# Sheet1.net
KiCad netlist of a schematic drawn in Altium Designer
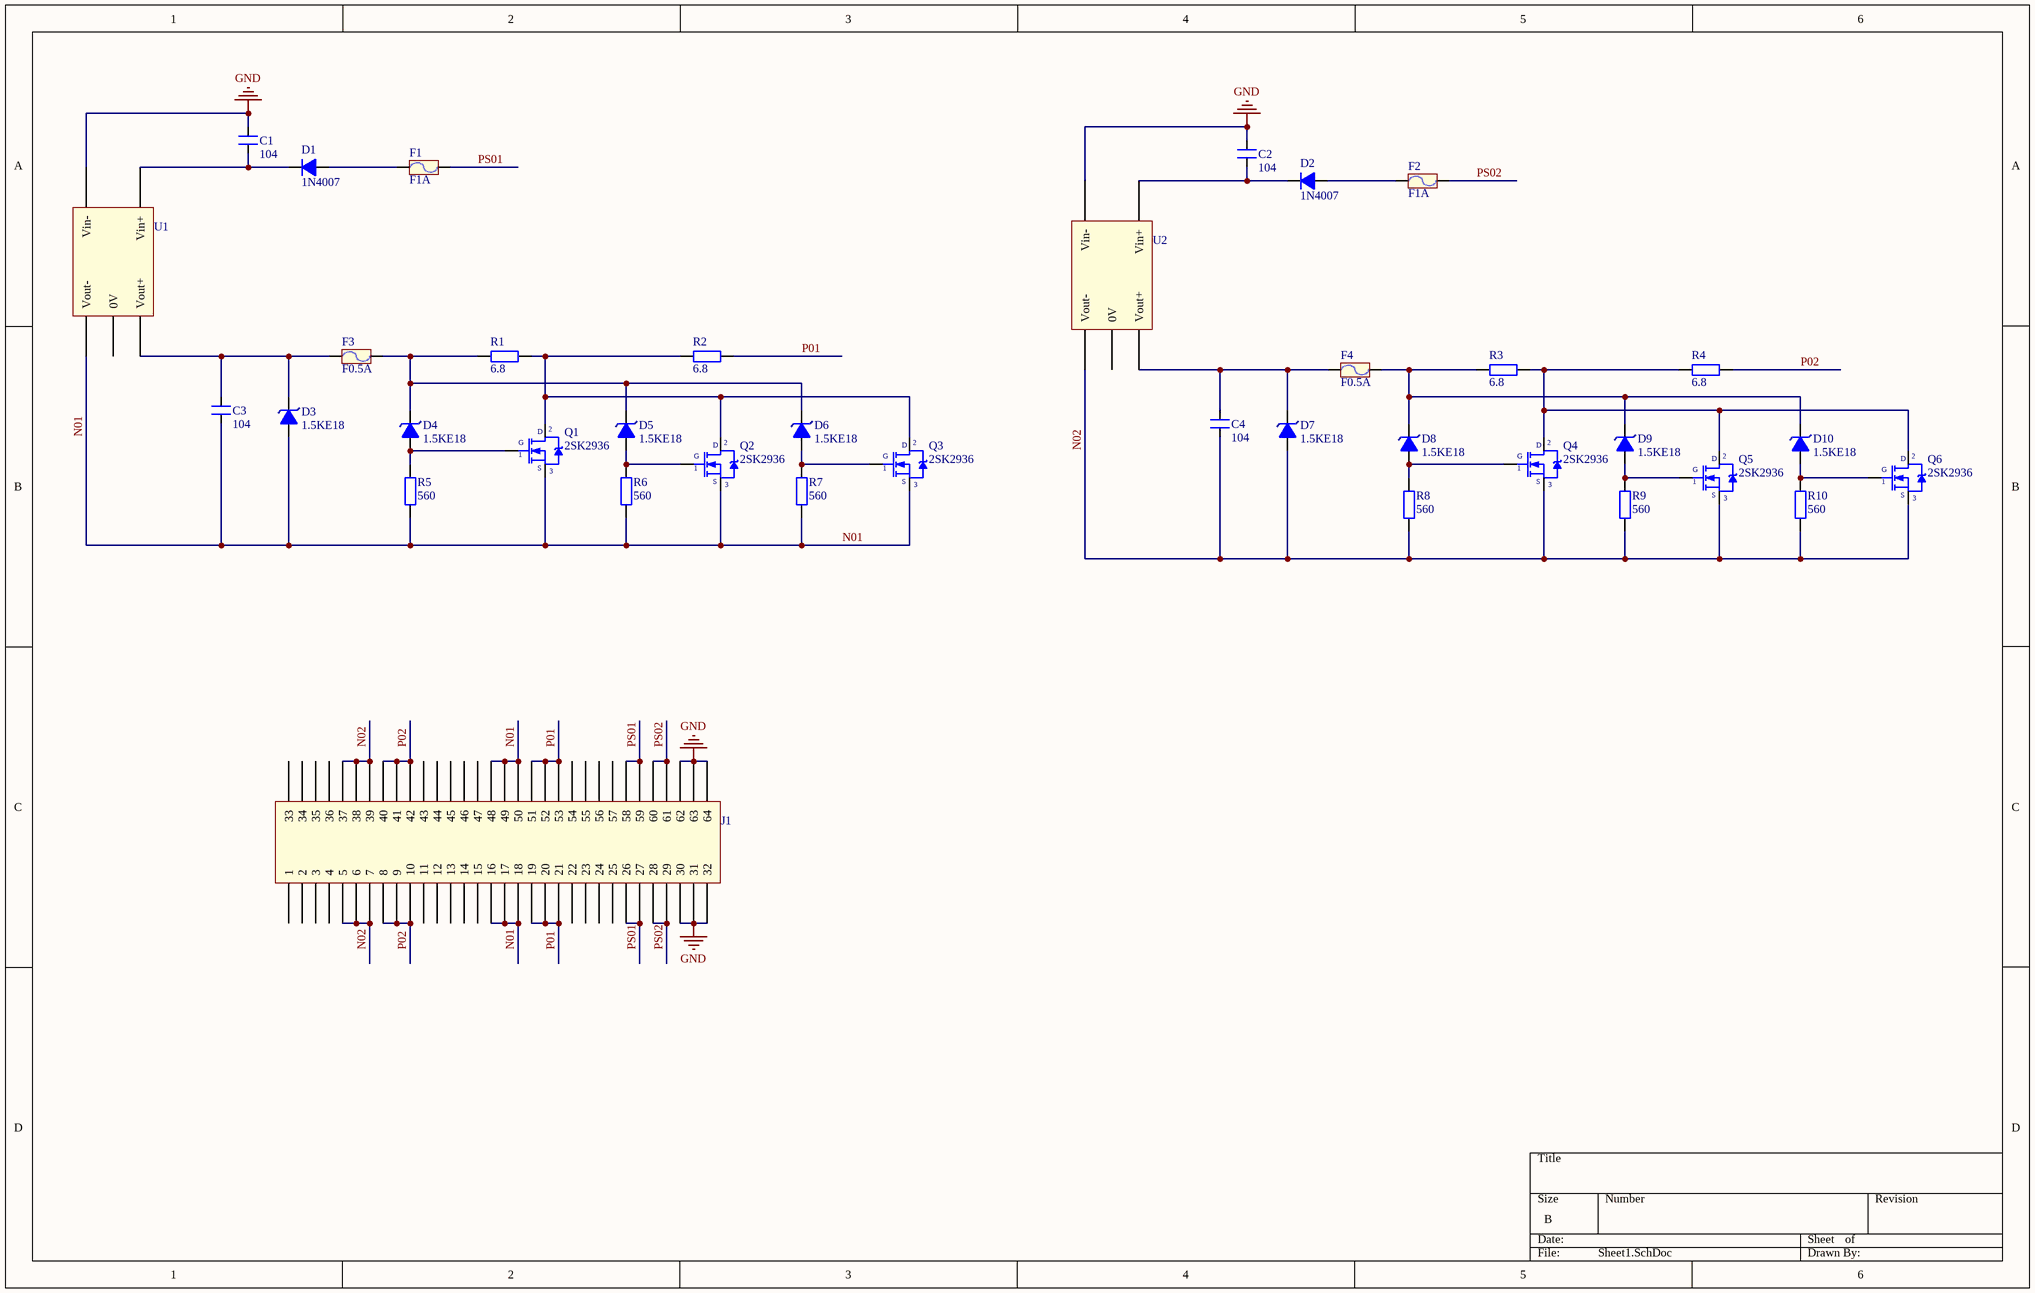
[diagram p0: Sheet1.SchDoc]

(export (version "E")
  (design (tool "Eeschema 10.0.6"))
  (components
    (comp (ref "C1")
      (value "104")
      (footprint "CN1")
      (description "Cremic For Xtal 1pF => 100pF")
      (libsource (lib "Binh_BK") (part "CAP"))
    )
    (comp (ref "C2")
      (value "104")
      (footprint "CN1")
      (description "Cremic For Xtal 1pF => 100pF")
      (libsource (lib "Binh_BK") (part "CAP"))
    )
    (comp (ref "C3")
      (value "104")
      (footprint "CN1")
      (description "Cremic For Xtal 1pF => 100pF")
      (libsource (lib "Binh_BK") (part "CAP"))
    )
    (comp (ref "C4")
      (value "104")
      (footprint "CN1")
      (description "Cremic For Xtal 1pF => 100pF")
      (libsource (lib "Binh_BK") (part "CAP"))
    )
    (comp (ref "D1")
      (value "1N4007")
      (footprint "D1A")
      (description "Diode 1A")
      (libsource (lib "Binh_BK") (part "D1A"))
    )
    (comp (ref "D2")
      (value "1N4007")
      (footprint "D1A")
      (description "Diode 1A")
      (libsource (lib "Binh_BK") (part "D1A"))
    )
    (comp (ref "D3") (value "1.5KE18") (footprint "D1A") (libsource (lib "Binh_BK") (part "Zener")))
    (comp (ref "D4") (value "1.5KE18") (footprint "D1A") (libsource (lib "Binh_BK") (part "Zener")))
    (comp (ref "D5") (value "1.5KE18") (footprint "D1A") (libsource (lib "Binh_BK") (part "Zener")))
    (comp (ref "D6") (value "1.5KE18") (footprint "D1A") (libsource (lib "Binh_BK") (part "Zener")))
    (comp (ref "D7") (value "1.5KE18") (footprint "D1A") (libsource (lib "Binh_BK") (part "Zener")))
    (comp (ref "D8") (value "1.5KE18") (footprint "D1A") (libsource (lib "Binh_BK") (part "Zener")))
    (comp (ref "D9") (value "1.5KE18") (footprint "D1A") (libsource (lib "Binh_BK") (part "Zener")))
    (comp (ref "D10") (value "1.5KE18") (footprint "D1A") (libsource (lib "Binh_BK") (part "Zener")))
    (comp (ref "F1")
      (value "F1A")
      (footprint "Fuse")
      (description "Fuse")
      (fields (field (name "DESIGNED BY") "VanDungEvn"))
      (libsource (lib "") (part "Fuse_1"))
    )
    (comp (ref "F2")
      (value "F1A")
      (footprint "Fuse")
      (description "Fuse")
      (fields (field (name "DESIGNED BY") "VanDungEvn"))
      (libsource (lib "") (part "Fuse_1"))
    )
    (comp (ref "F3")
      (value "F0.5A")
      (footprint "Fuse")
      (description "Fuse")
      (fields (field (name "DESIGNED BY") "VanDungEvn"))
      (libsource (lib "Binh_BK") (part "Fuse"))
    )
    (comp (ref "F4")
      (value "F0.5A")
      (footprint "Fuse")
      (description "Fuse")
      (fields (field (name "DESIGNED BY") "VanDungEvn"))
      (libsource (lib "Binh_BK") (part "Fuse"))
    )
    (comp (ref "J1")
      (value "Header 32x2")
      (footprint "Header32x2")
      (libsource (lib "dung_maker_2018") (part "Header 32x2"))
    )
    (comp (ref "Q1")
      (value "2SK2936")
      (footprint "QTO-220")
      (description "MOSFET N - CHANNEL 500V - 0.75 - 8A - TO-220")
      (libsource (lib "Binh_BK") (part "IRF840"))
    )
    (comp (ref "Q2")
      (value "2SK2936")
      (footprint "QTO-220")
      (description "MOSFET N - CHANNEL 500V - 0.75 - 8A - TO-220")
      (libsource (lib "Binh_BK") (part "IRF840"))
    )
    (comp (ref "Q3")
      (value "2SK2936")
      (footprint "QTO-220")
      (description "MOSFET N - CHANNEL 500V - 0.75 - 8A - TO-220")
      (libsource (lib "Binh_BK") (part "IRF840"))
    )
    (comp (ref "Q4")
      (value "2SK2936")
      (footprint "QTO-220")
      (description "MOSFET N - CHANNEL 500V - 0.75 - 8A - TO-220")
      (libsource (lib "Binh_BK") (part "IRF840"))
    )
    (comp (ref "Q5")
      (value "2SK2936")
      (footprint "QTO-220")
      (description "MOSFET N - CHANNEL 500V - 0.75 - 8A - TO-220")
      (libsource (lib "Binh_BK") (part "IRF840"))
    )
    (comp (ref "Q6")
      (value "2SK2936")
      (footprint "QTO-220")
      (description "MOSFET N - CHANNEL 500V - 0.75 - 8A - TO-220")
      (libsource (lib "Binh_BK") (part "IRF840"))
    )
    (comp (ref "R1")
      (value "6.8")
      (footprint "R5W")
      (description "Resistor 1/4W")
      (libsource (lib "Binh_BK") (part "R1/4W"))
    )
    (comp (ref "R2")
      (value "6.8")
      (footprint "R5W")
      (description "Resistor 1/4W")
      (libsource (lib "Binh_BK") (part "R1/4W"))
    )
    (comp (ref "R3")
      (value "6.8")
      (footprint "R5W")
      (description "Resistor 1/4W")
      (libsource (lib "Binh_BK") (part "R1/4W"))
    )
    (comp (ref "R4")
      (value "6.8")
      (footprint "R5W")
      (description "Resistor 1/4W")
      (libsource (lib "Binh_BK") (part "R1/4W"))
    )
    (comp (ref "R5")
      (value "560")
      (footprint "R1/4W")
      (description "Resistor 1/4W")
      (libsource (lib "Binh_BK") (part "R1/4W"))
    )
    (comp (ref "R6")
      (value "560")
      (footprint "R1/4W")
      (description "Resistor 1/4W")
      (libsource (lib "Binh_BK") (part "R1/4W"))
    )
    (comp (ref "R7")
      (value "560")
      (footprint "R1/4W")
      (description "Resistor 1/4W")
      (libsource (lib "Binh_BK") (part "R1/4W"))
    )
    (comp (ref "R8")
      (value "560")
      (footprint "R1/4W")
      (description "Resistor 1/4W")
      (libsource (lib "Binh_BK") (part "R1/4W"))
    )
    (comp (ref "R9")
      (value "560")
      (footprint "R1/4W")
      (description "Resistor 1/4W")
      (libsource (lib "Binh_BK") (part "R1/4W"))
    )
    (comp (ref "R10")
      (value "560")
      (footprint "R1/4W")
      (description "Resistor 1/4W")
      (libsource (lib "Binh_BK") (part "R1/4W"))
    )
    (comp (ref "U1")
      (value "WRx-YMD-6W")
      (footprint "WRB-YMD-6W")
      (libsource (lib "dung_maker_2018") (part "WRB-YMD-6W"))
    )
    (comp (ref "U2")
      (value "WRx-YMD-6W")
      (footprint "WRB-YMD-6W")
      (libsource (lib "dung_maker_2018") (part "WRB-YMD-6W"))
    )
  )
  (nets
    (net (code "1") (name "/N01") (class "Default")
      (node (ref "C3") (pin "1") (pinfunction "1_1") (pintype "passive"))
      (node (ref "D3") (pin "1") (pinfunction "A_1") (pintype "passive"))
      (node (ref "J1") (pin "16") (pinfunction "16_16") (pintype "passive"))
      (node (ref "J1") (pin "17") (pinfunction "17_17") (pintype "passive"))
      (node (ref "J1") (pin "18") (pinfunction "18_18") (pintype "passive"))
      (node (ref "J1") (pin "48") (pinfunction "48_48") (pintype "passive"))
      (node (ref "J1") (pin "49") (pinfunction "49_49") (pintype "passive"))
      (node (ref "J1") (pin "50") (pinfunction "50_50") (pintype "passive"))
      (node (ref "Q1") (pin "3") (pinfunction "S_3") (pintype "passive"))
      (node (ref "Q2") (pin "3") (pinfunction "S_3") (pintype "passive"))
      (node (ref "Q3") (pin "3") (pinfunction "S_3") (pintype "passive"))
      (node (ref "R5") (pin "1") (pinfunction "1_1") (pintype "passive"))
      (node (ref "R6") (pin "1") (pinfunction "1_1") (pintype "passive"))
      (node (ref "R7") (pin "1") (pinfunction "1_1") (pintype "passive"))
      (node (ref "U1") (pin "5") (pinfunction "Vout-_5") (pintype "passive"))
    )
    (net (code "2") (name "/N02") (class "Default")
      (node (ref "C4") (pin "1") (pinfunction "1_1") (pintype "passive"))
      (node (ref "D7") (pin "1") (pinfunction "A_1") (pintype "passive"))
      (node (ref "J1") (pin "37") (pinfunction "37_37") (pintype "passive"))
      (node (ref "J1") (pin "38") (pinfunction "38_38") (pintype "passive"))
      (node (ref "J1") (pin "39") (pinfunction "39_39") (pintype "passive"))
      (node (ref "J1") (pin "5") (pinfunction "5_5") (pintype "passive"))
      (node (ref "J1") (pin "6") (pinfunction "6_6") (pintype "passive"))
      (node (ref "J1") (pin "7") (pinfunction "7_7") (pintype "passive"))
      (node (ref "Q4") (pin "3") (pinfunction "S_3") (pintype "passive"))
      (node (ref "Q5") (pin "3") (pinfunction "S_3") (pintype "passive"))
      (node (ref "Q6") (pin "3") (pinfunction "S_3") (pintype "passive"))
      (node (ref "R10") (pin "1") (pinfunction "1_1") (pintype "passive"))
      (node (ref "R8") (pin "1") (pinfunction "1_1") (pintype "passive"))
      (node (ref "R9") (pin "1") (pinfunction "1_1") (pintype "passive"))
      (node (ref "U2") (pin "5") (pinfunction "Vout-_5") (pintype "passive"))
    )
    (net (code "3") (name "/P01") (class "Default")
      (node (ref "J1") (pin "19") (pinfunction "19_19") (pintype "passive"))
      (node (ref "J1") (pin "20") (pinfunction "20_20") (pintype "passive"))
      (node (ref "J1") (pin "21") (pinfunction "21_21") (pintype "passive"))
      (node (ref "J1") (pin "51") (pinfunction "51_51") (pintype "passive"))
      (node (ref "J1") (pin "52") (pinfunction "52_52") (pintype "passive"))
      (node (ref "J1") (pin "53") (pinfunction "53_53") (pintype "passive"))
      (node (ref "R2") (pin "1") (pinfunction "1_1") (pintype "passive"))
    )
    (net (code "4") (name "/P02") (class "Default")
      (node (ref "J1") (pin "10") (pinfunction "10_10") (pintype "passive"))
      (node (ref "J1") (pin "40") (pinfunction "40_40") (pintype "passive"))
      (node (ref "J1") (pin "41") (pinfunction "41_41") (pintype "passive"))
      (node (ref "J1") (pin "42") (pinfunction "42_42") (pintype "passive"))
      (node (ref "J1") (pin "8") (pinfunction "8_8") (pintype "passive"))
      (node (ref "J1") (pin "9") (pinfunction "9_9") (pintype "passive"))
      (node (ref "R4") (pin "1") (pinfunction "1_1") (pintype "passive"))
    )
    (net (code "5") (name "/PS01") (class "Default")
      (node (ref "F1") (pin "2") (pinfunction "2_2") (pintype "passive"))
      (node (ref "J1") (pin "26") (pinfunction "26_26") (pintype "passive"))
      (node (ref "J1") (pin "27") (pinfunction "27_27") (pintype "passive"))
      (node (ref "J1") (pin "58") (pinfunction "58_58") (pintype "passive"))
      (node (ref "J1") (pin "59") (pinfunction "59_59") (pintype "passive"))
    )
    (net (code "6") (name "/PS02") (class "Default")
      (node (ref "F2") (pin "2") (pinfunction "2_2") (pintype "passive"))
      (node (ref "J1") (pin "28") (pinfunction "28_28") (pintype "passive"))
      (node (ref "J1") (pin "29") (pinfunction "29_29") (pintype "passive"))
      (node (ref "J1") (pin "60") (pinfunction "60_60") (pintype "passive"))
      (node (ref "J1") (pin "61") (pinfunction "61_61") (pintype "passive"))
    )
    (net (code "7") (name "GND") (class "Default")
      (node (ref "C1") (pin "2") (pinfunction "2_2") (pintype "passive"))
      (node (ref "C2") (pin "2") (pinfunction "2_2") (pintype "passive"))
      (node (ref "J1") (pin "30") (pinfunction "30_30") (pintype "passive"))
      (node (ref "J1") (pin "31") (pinfunction "31_31") (pintype "passive"))
      (node (ref "J1") (pin "32") (pinfunction "32_32") (pintype "passive"))
      (node (ref "J1") (pin "62") (pinfunction "62_62") (pintype "passive"))
      (node (ref "J1") (pin "63") (pinfunction "63_63") (pintype "passive"))
      (node (ref "J1") (pin "64") (pinfunction "64_64") (pintype "passive"))
      (node (ref "U1") (pin "1") (pinfunction "Vin-_1") (pintype "passive"))
      (node (ref "U2") (pin "1") (pinfunction "Vin-_1") (pintype "passive"))
    )
    (net (code "8") (name "Net-(D1-A)") (class "Default")
      (node (ref "D1") (pin "1") (pinfunction "A_1") (pintype "passive"))
      (node (ref "F1") (pin "1") (pinfunction "1_1") (pintype "passive"))
    )
    (net (code "9") (name "Net-(D1-K)") (class "Default")
      (node (ref "C1") (pin "1") (pinfunction "1_1") (pintype "passive"))
      (node (ref "D1") (pin "2") (pinfunction "K_2") (pintype "passive"))
      (node (ref "U1") (pin "2") (pinfunction "Vin+_2") (pintype "passive"))
    )
    (net (code "10") (name "Net-(D2-A)") (class "Default")
      (node (ref "D2") (pin "1") (pinfunction "A_1") (pintype "passive"))
      (node (ref "F2") (pin "1") (pinfunction "1_1") (pintype "passive"))
    )
    (net (code "11") (name "Net-(D2-K)") (class "Default")
      (node (ref "C2") (pin "1") (pinfunction "1_1") (pintype "passive"))
      (node (ref "D2") (pin "2") (pinfunction "K_2") (pintype "passive"))
      (node (ref "U2") (pin "2") (pinfunction "Vin+_2") (pintype "passive"))
    )
    (net (code "12") (name "Net-(D3-K)") (class "Default")
      (node (ref "C3") (pin "2") (pinfunction "2_2") (pintype "passive"))
      (node (ref "D3") (pin "2") (pinfunction "K_2") (pintype "passive"))
      (node (ref "F3") (pin "2") (pinfunction "2_2") (pintype "passive"))
      (node (ref "U1") (pin "3") (pinfunction "Vout+_3") (pintype "passive"))
    )
    (net (code "13") (name "Net-(D4-A)") (class "Default")
      (node (ref "D4") (pin "1") (pinfunction "A_1") (pintype "passive"))
      (node (ref "Q1") (pin "1") (pinfunction "G_1") (pintype "passive"))
      (node (ref "R5") (pin "2") (pinfunction "2_2") (pintype "passive"))
    )
    (net (code "14") (name "Net-(D4-K)") (class "Default")
      (node (ref "D4") (pin "2") (pinfunction "K_2") (pintype "passive"))
      (node (ref "D5") (pin "2") (pinfunction "K_2") (pintype "passive"))
      (node (ref "D6") (pin "2") (pinfunction "K_2") (pintype "passive"))
      (node (ref "F3") (pin "1") (pinfunction "1_1") (pintype "passive"))
      (node (ref "R1") (pin "2") (pinfunction "2_2") (pintype "passive"))
    )
    (net (code "15") (name "Net-(D5-A)") (class "Default")
      (node (ref "D5") (pin "1") (pinfunction "A_1") (pintype "passive"))
      (node (ref "Q2") (pin "1") (pinfunction "G_1") (pintype "passive"))
      (node (ref "R6") (pin "2") (pinfunction "2_2") (pintype "passive"))
    )
    (net (code "16") (name "Net-(D6-A)") (class "Default")
      (node (ref "D6") (pin "1") (pinfunction "A_1") (pintype "passive"))
      (node (ref "Q3") (pin "1") (pinfunction "G_1") (pintype "passive"))
      (node (ref "R7") (pin "2") (pinfunction "2_2") (pintype "passive"))
    )
    (net (code "17") (name "Net-(D7-K)") (class "Default")
      (node (ref "C4") (pin "2") (pinfunction "2_2") (pintype "passive"))
      (node (ref "D7") (pin "2") (pinfunction "K_2") (pintype "passive"))
      (node (ref "F4") (pin "2") (pinfunction "2_2") (pintype "passive"))
      (node (ref "U2") (pin "3") (pinfunction "Vout+_3") (pintype "passive"))
    )
    (net (code "18") (name "Net-(D8-A)") (class "Default")
      (node (ref "D8") (pin "1") (pinfunction "A_1") (pintype "passive"))
      (node (ref "Q4") (pin "1") (pinfunction "G_1") (pintype "passive"))
      (node (ref "R8") (pin "2") (pinfunction "2_2") (pintype "passive"))
    )
    (net (code "19") (name "Net-(D9-A)") (class "Default")
      (node (ref "D9") (pin "1") (pinfunction "A_1") (pintype "passive"))
      (node (ref "Q5") (pin "1") (pinfunction "G_1") (pintype "passive"))
      (node (ref "R9") (pin "2") (pinfunction "2_2") (pintype "passive"))
    )
    (net (code "20") (name "Net-(D10-A)") (class "Default")
      (node (ref "D10") (pin "1") (pinfunction "A_1") (pintype "passive"))
      (node (ref "Q6") (pin "1") (pinfunction "G_1") (pintype "passive"))
      (node (ref "R10") (pin "2") (pinfunction "2_2") (pintype "passive"))
    )
    (net (code "21") (name "Net-(D10-K)") (class "Default")
      (node (ref "D10") (pin "2") (pinfunction "K_2") (pintype "passive"))
      (node (ref "D8") (pin "2") (pinfunction "K_2") (pintype "passive"))
      (node (ref "D9") (pin "2") (pinfunction "K_2") (pintype "passive"))
      (node (ref "F4") (pin "1") (pinfunction "1_1") (pintype "passive"))
      (node (ref "R3") (pin "2") (pinfunction "2_2") (pintype "passive"))
    )
    (net (code "22") (name "Net-(Q1-D)") (class "Default")
      (node (ref "Q1") (pin "2") (pinfunction "D_2") (pintype "passive"))
      (node (ref "Q2") (pin "2") (pinfunction "D_2") (pintype "passive"))
      (node (ref "Q3") (pin "2") (pinfunction "D_2") (pintype "passive"))
      (node (ref "R1") (pin "1") (pinfunction "1_1") (pintype "passive"))
      (node (ref "R2") (pin "2") (pinfunction "2_2") (pintype "passive"))
    )
    (net (code "23") (name "Net-(Q4-D)") (class "Default")
      (node (ref "Q4") (pin "2") (pinfunction "D_2") (pintype "passive"))
      (node (ref "Q5") (pin "2") (pinfunction "D_2") (pintype "passive"))
      (node (ref "Q6") (pin "2") (pinfunction "D_2") (pintype "passive"))
      (node (ref "R3") (pin "1") (pinfunction "1_1") (pintype "passive"))
      (node (ref "R4") (pin "2") (pinfunction "2_2") (pintype "passive"))
    )
    (net (code "24") (name "unconnected-(J1-Pad1)") (class "Default")
      (node (ref "J1") (pin "1") (pinfunction "1_1") (pintype "passive"))
    )
    (net (code "25") (name "unconnected-(J1-Pad2)") (class "Default")
      (node (ref "J1") (pin "2") (pinfunction "2_2") (pintype "passive"))
    )
    (net (code "26") (name "unconnected-(J1-Pad3)") (class "Default")
      (node (ref "J1") (pin "3") (pinfunction "3_3") (pintype "passive"))
    )
    (net (code "27") (name "unconnected-(J1-Pad4)") (class "Default")
      (node (ref "J1") (pin "4") (pinfunction "4_4") (pintype "passive"))
    )
    (net (code "28") (name "unconnected-(J1-Pad11)") (class "Default")
      (node (ref "J1") (pin "11") (pinfunction "11_11") (pintype "passive"))
    )
    (net (code "29") (name "unconnected-(J1-Pad12)") (class "Default")
      (node (ref "J1") (pin "12") (pinfunction "12_12") (pintype "passive"))
    )
    (net (code "30") (name "unconnected-(J1-Pad13)") (class "Default")
      (node (ref "J1") (pin "13") (pinfunction "13_13") (pintype "passive"))
    )
    (net (code "31") (name "unconnected-(J1-Pad14)") (class "Default")
      (node (ref "J1") (pin "14") (pinfunction "14_14") (pintype "passive"))
    )
    (net (code "32") (name "unconnected-(J1-Pad15)") (class "Default")
      (node (ref "J1") (pin "15") (pinfunction "15_15") (pintype "passive"))
    )
    (net (code "33") (name "unconnected-(J1-Pad22)") (class "Default")
      (node (ref "J1") (pin "22") (pinfunction "22_22") (pintype "passive"))
    )
    (net (code "34") (name "unconnected-(J1-Pad23)") (class "Default")
      (node (ref "J1") (pin "23") (pinfunction "23_23") (pintype "passive"))
    )
    (net (code "35") (name "unconnected-(J1-Pad24)") (class "Default")
      (node (ref "J1") (pin "24") (pinfunction "24_24") (pintype "passive"))
    )
    (net (code "36") (name "unconnected-(J1-Pad25)") (class "Default")
      (node (ref "J1") (pin "25") (pinfunction "25_25") (pintype "passive"))
    )
    (net (code "37") (name "unconnected-(J1-Pad33)") (class "Default")
      (node (ref "J1") (pin "33") (pinfunction "33_33") (pintype "passive"))
    )
    (net (code "38") (name "unconnected-(J1-Pad34)") (class "Default")
      (node (ref "J1") (pin "34") (pinfunction "34_34") (pintype "passive"))
    )
    (net (code "39") (name "unconnected-(J1-Pad35)") (class "Default")
      (node (ref "J1") (pin "35") (pinfunction "35_35") (pintype "passive"))
    )
    (net (code "40") (name "unconnected-(J1-Pad36)") (class "Default")
      (node (ref "J1") (pin "36") (pinfunction "36_36") (pintype "passive"))
    )
    (net (code "41") (name "unconnected-(J1-Pad43)") (class "Default")
      (node (ref "J1") (pin "43") (pinfunction "43_43") (pintype "passive"))
    )
    (net (code "42") (name "unconnected-(J1-Pad44)") (class "Default")
      (node (ref "J1") (pin "44") (pinfunction "44_44") (pintype "passive"))
    )
    (net (code "43") (name "unconnected-(J1-Pad45)") (class "Default")
      (node (ref "J1") (pin "45") (pinfunction "45_45") (pintype "passive"))
    )
    (net (code "44") (name "unconnected-(J1-Pad46)") (class "Default")
      (node (ref "J1") (pin "46") (pinfunction "46_46") (pintype "passive"))
    )
    (net (code "45") (name "unconnected-(J1-Pad47)") (class "Default")
      (node (ref "J1") (pin "47") (pinfunction "47_47") (pintype "passive"))
    )
    (net (code "46") (name "unconnected-(J1-Pad54)") (class "Default")
      (node (ref "J1") (pin "54") (pinfunction "54_54") (pintype "passive"))
    )
    (net (code "47") (name "unconnected-(J1-Pad55)") (class "Default")
      (node (ref "J1") (pin "55") (pinfunction "55_55") (pintype "passive"))
    )
    (net (code "48") (name "unconnected-(J1-Pad56)") (class "Default")
      (node (ref "J1") (pin "56") (pinfunction "56_56") (pintype "passive"))
    )
    (net (code "49") (name "unconnected-(J1-Pad57)") (class "Default")
      (node (ref "J1") (pin "57") (pinfunction "57_57") (pintype "passive"))
    )
    (net (code "50") (name "unconnected-(U1-0V-Pad4)") (class "Default")
      (node (ref "U1") (pin "4") (pinfunction "0V_4") (pintype "passive"))
    )
    (net (code "51") (name "unconnected-(U2-0V-Pad4)") (class "Default")
      (node (ref "U2") (pin "4") (pinfunction "0V_4") (pintype "passive"))
    )
  )
)
